# Zabezpieczenie_samochodowe_2021-03-07.net
KiCad netlist of a schematic drawn in EasyEDA
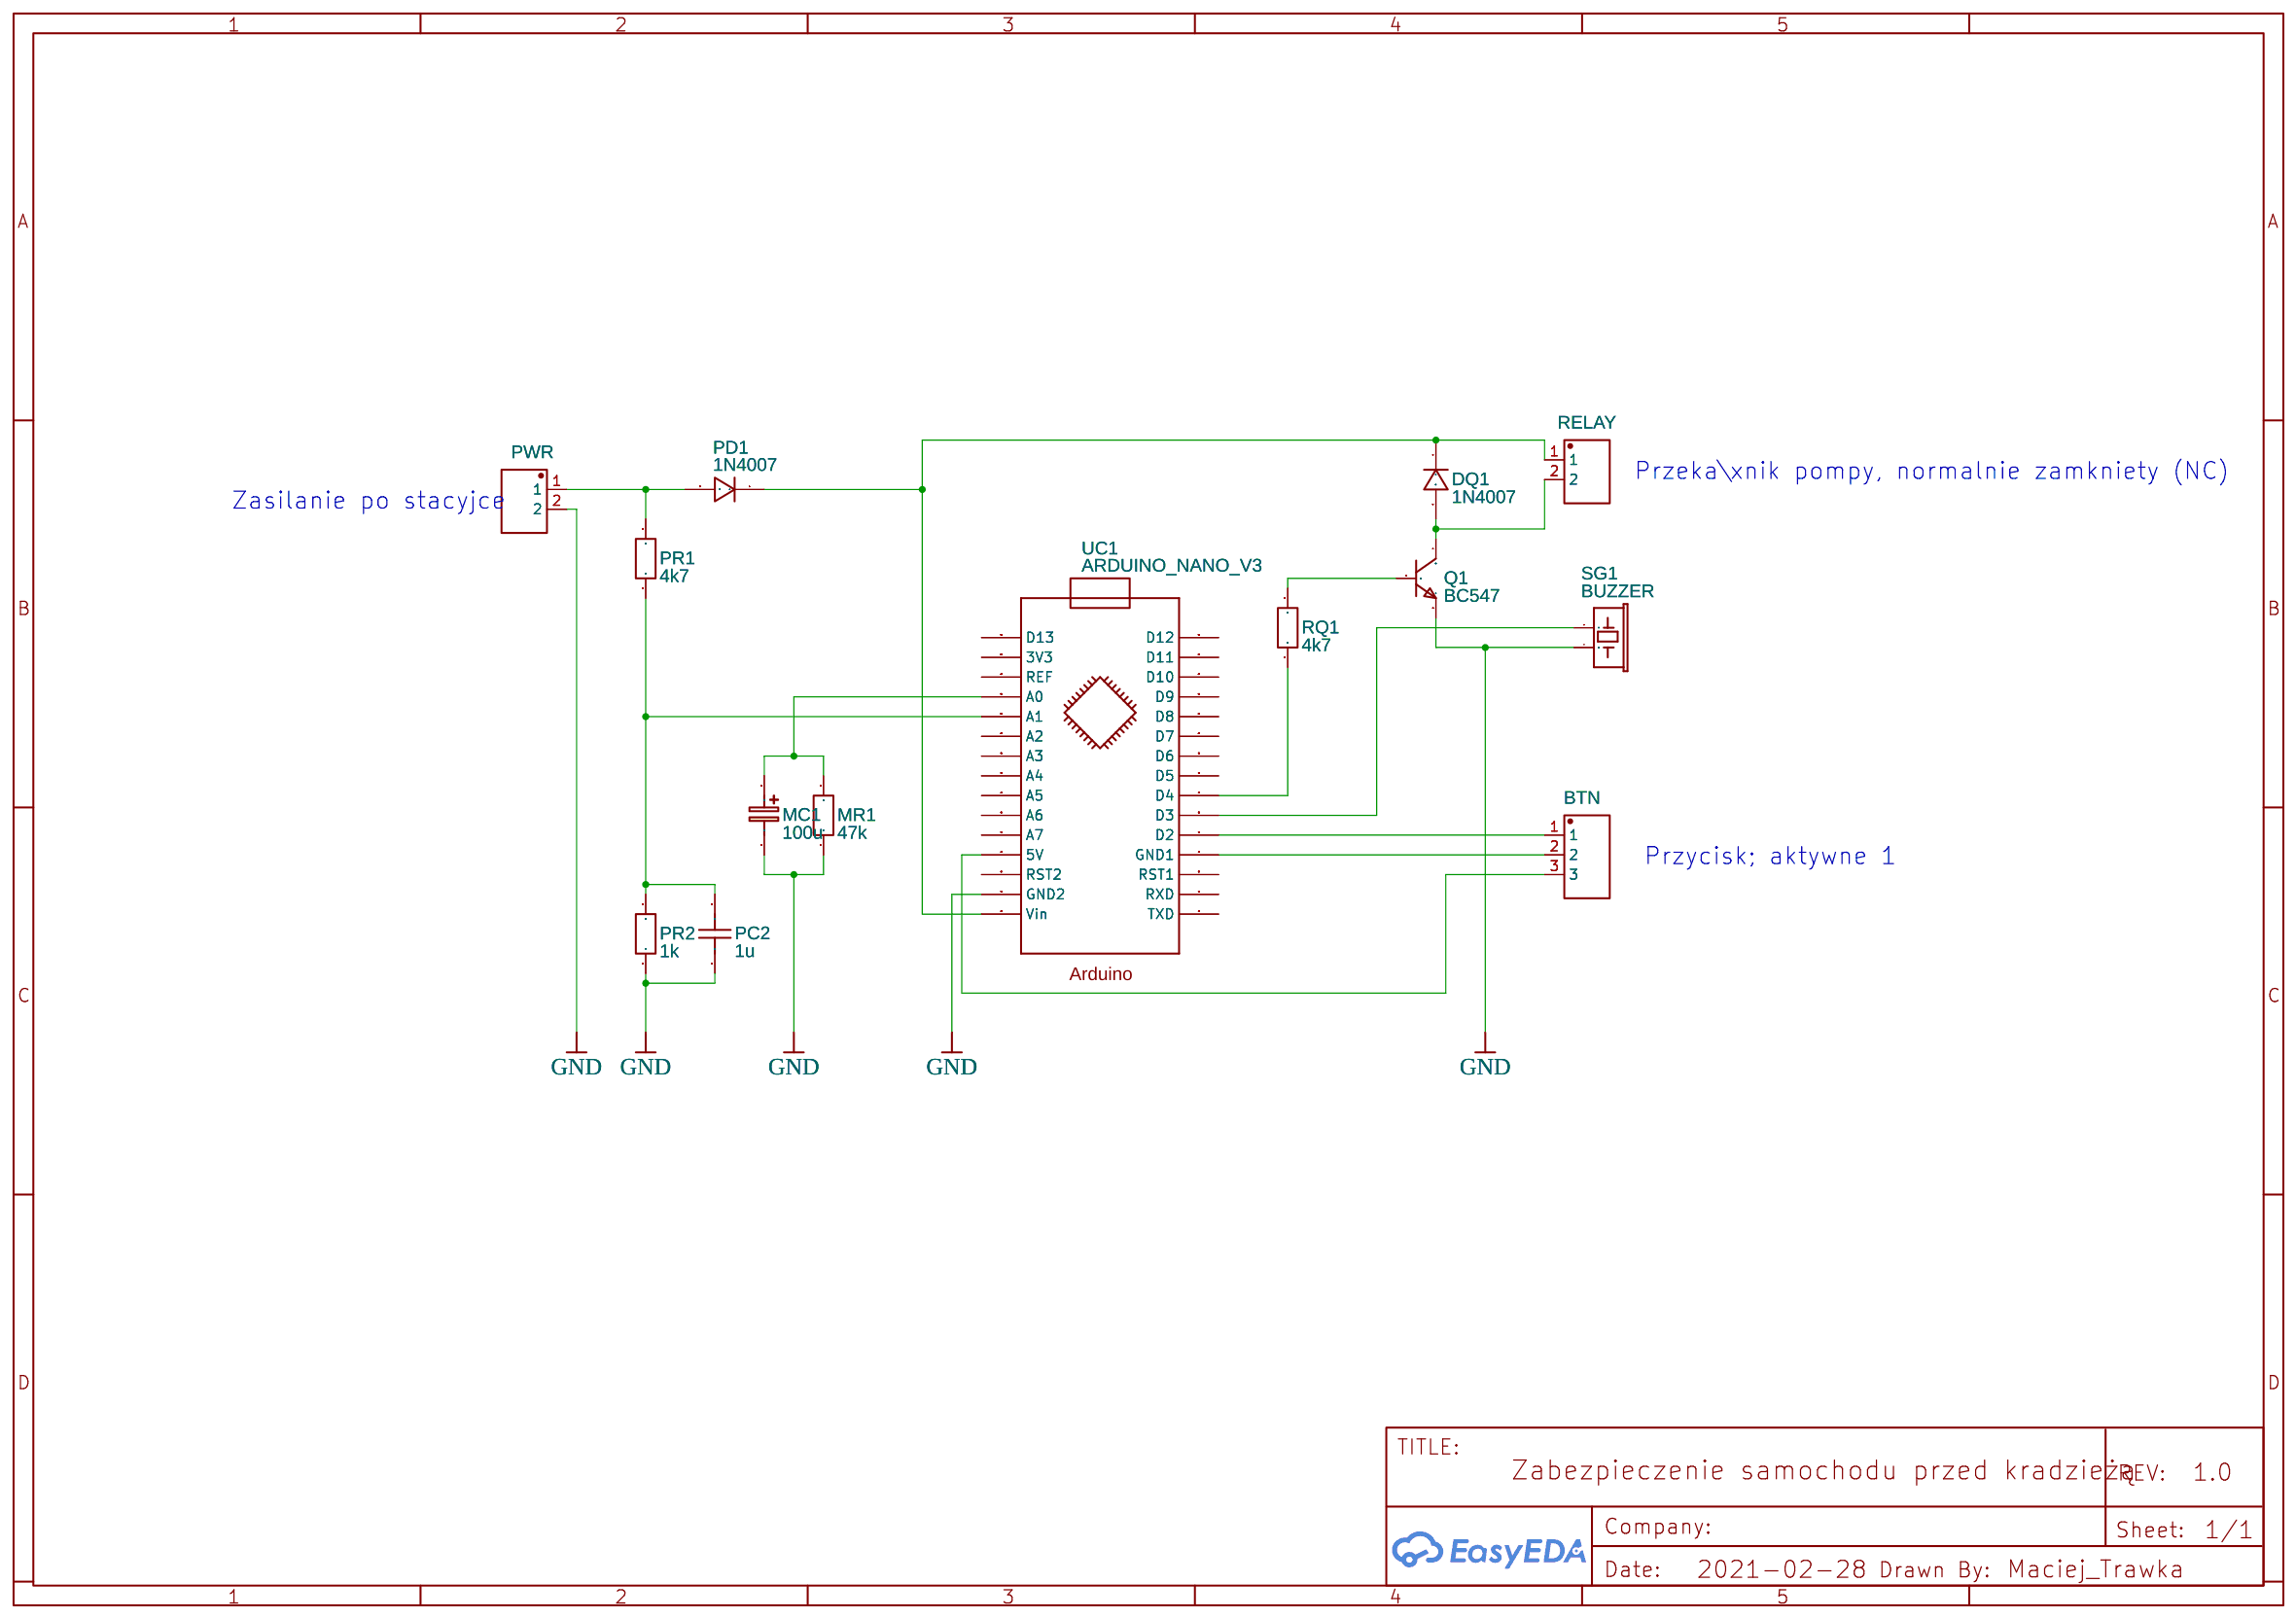
[diagram p0: schematic sheet]

(export (version "E")
  (design (tool "Eeschema 10.0.6"))
  (components
    (comp (ref "BTN")
      (value "WJ15EDGVC-3P")
      (fields (field (name "BOM_Supplier Part") "C8389"))
      (libsource (lib "") (part "Unknown_790_-380"))
    )
    (comp (ref "DQ1")
      (value "1N4007")
      (fields (field (name "BOM_Supplier Part") "C106903"))
      (libsource (lib "") (part "1N4007_1"))
    )
    (comp (ref "MC1") (value "100u") (libsource (lib "") (part "CE_TH_D5.0×F2.0_EU")))
    (comp (ref "MR1") (value "47k") (libsource (lib "") (part "R_AXIAL-0.3_EU")))
    (comp (ref "PC2") (value "1u") (libsource (lib "") (part "C_RAD-0.2_US")))
    (comp (ref "PD1")
      (value "1N4007")
      (fields (field (name "BOM_Supplier Part") "C106903"))
      (libsource (lib "") (part "1N4007"))
    )
    (comp (ref "PR1") (value "4k7") (libsource (lib "") (part "R_AXIAL-0.3_EU_1")))
    (comp (ref "PR2") (value "1k") (libsource (lib "") (part "R_AXIAL-0.3_EU_1")))
    (comp (ref "PWR")
      (value "WJ15EDGVC-3.81-2P")
      (fields (field (name "BOM_Supplier Part") "C8396"))
      (libsource (lib "") (part "Unknown_265_-560"))
    )
    (comp (ref "Q1")
      (value "BC547")
      (fields (field (name "BOM_Manufacturer Part") "BC547BTA") (field (name "BOM_Supplier Part") "C258144"))
      (libsource (lib "") (part "BC547"))
    )
    (comp (ref "RELAY")
      (value "WJ15EDGVC-3.81-2P")
      (fields (field (name "BOM_Supplier Part") "C8396"))
      (libsource (lib "") (part "Unknown_790_-575"))
    )
    (comp (ref "RQ1") (value "4k7") (libsource (lib "") (part "R_AXIAL-0.3_EU_2")))
    (comp (ref "SG1") (value "BUZZER") (libsource (lib "") (part "BUZZER")))
    (comp (ref "UC1")
      (value "ARDUINO_NANO_V3")
      (fields (field (name "BOM_Manufacturer Part") "arduino_nano1"))
      (libsource (lib "") (part "ARDUINO_NANO_V3"))
    )
  )
  (nets
    (net (code "1") (name "GND") (class "Default")
      (node (ref "MC1") (pin "2") (pinfunction "2_2") (pintype "unspecified"))
      (node (ref "MR1") (pin "1") (pinfunction "1_1") (pintype "unspecified"))
      (node (ref "PC2") (pin "1") (pinfunction "1_1") (pintype "unspecified"))
      (node (ref "PR2") (pin "1") (pinfunction "1_1") (pintype "unspecified"))
      (node (ref "PWR") (pin "2") (pinfunction "2_2") (pintype "unspecified"))
      (node (ref "Q1") (pin "3") (pinfunction "E_3") (pintype "unspecified"))
      (node (ref "SG1") (pin "-") (pinfunction "2_-") (pintype "unspecified"))
      (node (ref "UC1") (pin "J2.2") (pinfunction "GND2_J2.2") (pintype "unspecified"))
    )
    (net (code "2") (name "Net-(PD1-Pad2)") (class "Default")
      (node (ref "PD1") (pin "2") (pinfunction "2_2") (pintype "unspecified"))
      (node (ref "PR1") (pin "2") (pinfunction "2_2") (pintype "unspecified"))
      (node (ref "PWR") (pin "1") (pinfunction "1_1") (pintype "unspecified"))
    )
    (net (code "3") (name "Net-(Q1-B)") (class "Default")
      (node (ref "Q1") (pin "2") (pinfunction "B_2") (pintype "unspecified"))
      (node (ref "RQ1") (pin "2") (pinfunction "2_2") (pintype "unspecified"))
    )
    (net (code "4") (name "Net-(Q1-C)") (class "Default")
      (node (ref "DQ1") (pin "2") (pinfunction "2_2") (pintype "unspecified"))
      (node (ref "Q1") (pin "1") (pinfunction "C_1") (pintype "unspecified"))
      (node (ref "RELAY") (pin "2") (pinfunction "2_2") (pintype "unspecified"))
    )
    (net (code "5") (name "Net-(SG1-1)") (class "Default")
      (node (ref "SG1") (pin "+") (pinfunction "1_+") (pintype "unspecified"))
      (node (ref "UC1") (pin "J1.6") (pinfunction "D3_J1.6") (pintype "unspecified"))
    )
    (net (code "6") (name "Net-(UC1-5V)") (class "Default")
      (node (ref "BTN") (pin "3") (pinfunction "3_3") (pintype "unspecified"))
      (node (ref "UC1") (pin "J2.4") (pinfunction "5V_J2.4") (pintype "unspecified"))
    )
    (net (code "7") (name "Net-(UC1-A0)") (class "Default")
      (node (ref "MC1") (pin "1") (pinfunction "1_1") (pintype "unspecified"))
      (node (ref "MR1") (pin "2") (pinfunction "2_2") (pintype "unspecified"))
      (node (ref "UC1") (pin "J2.12") (pinfunction "A0_J2.12") (pintype "unspecified"))
    )
    (net (code "8") (name "Net-(UC1-A1)") (class "Default")
      (node (ref "PC2") (pin "2") (pinfunction "2_2") (pintype "unspecified"))
      (node (ref "PR1") (pin "1") (pinfunction "1_1") (pintype "unspecified"))
      (node (ref "PR2") (pin "2") (pinfunction "2_2") (pintype "unspecified"))
      (node (ref "UC1") (pin "J2.11") (pinfunction "A1_J2.11") (pintype "unspecified"))
    )
    (net (code "9") (name "Net-(UC1-D2)") (class "Default")
      (node (ref "BTN") (pin "1") (pinfunction "1_1") (pintype "unspecified"))
      (node (ref "UC1") (pin "J1.5") (pinfunction "D2_J1.5") (pintype "unspecified"))
    )
    (net (code "10") (name "Net-(UC1-D4)") (class "Default")
      (node (ref "RQ1") (pin "1") (pinfunction "1_1") (pintype "unspecified"))
      (node (ref "UC1") (pin "J1.7") (pinfunction "D4_J1.7") (pintype "unspecified"))
    )
    (net (code "11") (name "Net-(UC1-GND1)") (class "Default")
      (node (ref "BTN") (pin "2") (pinfunction "2_2") (pintype "unspecified"))
      (node (ref "UC1") (pin "J1.4") (pinfunction "GND1_J1.4") (pintype "unspecified"))
    )
    (net (code "12") (name "Net-(UC1-Vin)") (class "Default")
      (node (ref "DQ1") (pin "1") (pinfunction "1_1") (pintype "unspecified"))
      (node (ref "PD1") (pin "1") (pinfunction "1_1") (pintype "unspecified"))
      (node (ref "RELAY") (pin "1") (pinfunction "1_1") (pintype "unspecified"))
      (node (ref "UC1") (pin "J2.1") (pinfunction "Vin_J2.1") (pintype "unspecified"))
    )
    (net (code "13") (name "unconnected-(UC1-3V3-PadJ2.14)") (class "Default")
      (node (ref "UC1") (pin "J2.14") (pinfunction "3V3_J2.14") (pintype "unspecified"))
    )
    (net (code "14") (name "unconnected-(UC1-A2-PadJ2.10)") (class "Default")
      (node (ref "UC1") (pin "J2.10") (pinfunction "A2_J2.10") (pintype "unspecified"))
    )
    (net (code "15") (name "unconnected-(UC1-A3-PadJ2.9)") (class "Default")
      (node (ref "UC1") (pin "J2.9") (pinfunction "A3_J2.9") (pintype "unspecified"))
    )
    (net (code "16") (name "unconnected-(UC1-A4-PadJ2.8)") (class "Default")
      (node (ref "UC1") (pin "J2.8") (pinfunction "A4_J2.8") (pintype "unspecified"))
    )
    (net (code "17") (name "unconnected-(UC1-A5-PadJ2.7)") (class "Default")
      (node (ref "UC1") (pin "J2.7") (pinfunction "A5_J2.7") (pintype "unspecified"))
    )
    (net (code "18") (name "unconnected-(UC1-A6-PadJ2.6)") (class "Default")
      (node (ref "UC1") (pin "J2.6") (pinfunction "A6_J2.6") (pintype "unspecified"))
    )
    (net (code "19") (name "unconnected-(UC1-A7-PadJ2.5)") (class "Default")
      (node (ref "UC1") (pin "J2.5") (pinfunction "A7_J2.5") (pintype "unspecified"))
    )
    (net (code "20") (name "unconnected-(UC1-D5-PadJ1.8)") (class "Default")
      (node (ref "UC1") (pin "J1.8") (pinfunction "D5_J1.8") (pintype "unspecified"))
    )
    (net (code "21") (name "unconnected-(UC1-D6-PadJ1.9)") (class "Default")
      (node (ref "UC1") (pin "J1.9") (pinfunction "D6_J1.9") (pintype "unspecified"))
    )
    (net (code "22") (name "unconnected-(UC1-D7-PadJ1.10)") (class "Default")
      (node (ref "UC1") (pin "J1.10") (pinfunction "D7_J1.10") (pintype "unspecified"))
    )
    (net (code "23") (name "unconnected-(UC1-D8-PadJ1.11)") (class "Default")
      (node (ref "UC1") (pin "J1.11") (pinfunction "D8_J1.11") (pintype "unspecified"))
    )
    (net (code "24") (name "unconnected-(UC1-D9-PadJ1.12)") (class "Default")
      (node (ref "UC1") (pin "J1.12") (pinfunction "D9_J1.12") (pintype "unspecified"))
    )
    (net (code "25") (name "unconnected-(UC1-D10-PadJ1.13)") (class "Default")
      (node (ref "UC1") (pin "J1.13") (pinfunction "D10_J1.13") (pintype "unspecified"))
    )
    (net (code "26") (name "unconnected-(UC1-D11-PadJ1.14)") (class "Default")
      (node (ref "UC1") (pin "J1.14") (pinfunction "D11_J1.14") (pintype "unspecified"))
    )
    (net (code "27") (name "unconnected-(UC1-D12-PadJ1.15)") (class "Default")
      (node (ref "UC1") (pin "J1.15") (pinfunction "D12_J1.15") (pintype "unspecified"))
    )
    (net (code "28") (name "unconnected-(UC1-D13-PadJ2.15)") (class "Default")
      (node (ref "UC1") (pin "J2.15") (pinfunction "D13_J2.15") (pintype "unspecified"))
    )
    (net (code "29") (name "unconnected-(UC1-REF-PadJ2.13)") (class "Default")
      (node (ref "UC1") (pin "J2.13") (pinfunction "REF_J2.13") (pintype "unspecified"))
    )
    (net (code "30") (name "unconnected-(UC1-RST1-PadJ1.3)") (class "Default")
      (node (ref "UC1") (pin "J1.3") (pinfunction "RST1_J1.3") (pintype "unspecified"))
    )
    (net (code "31") (name "unconnected-(UC1-RST2-PadJ2.3)") (class "Default")
      (node (ref "UC1") (pin "J2.3") (pinfunction "RST2_J2.3") (pintype "unspecified"))
    )
    (net (code "32") (name "unconnected-(UC1-RXD-PadJ1.2)") (class "Default")
      (node (ref "UC1") (pin "J1.2") (pinfunction "RXD_J1.2") (pintype "unspecified"))
    )
    (net (code "33") (name "unconnected-(UC1-TXD-PadJ1.1)") (class "Default")
      (node (ref "UC1") (pin "J1.1") (pinfunction "TXD_J1.1") (pintype "unspecified"))
    )
  )
)
